# CON1.net
KiCad netlist of a schematic drawn in Altium Designer
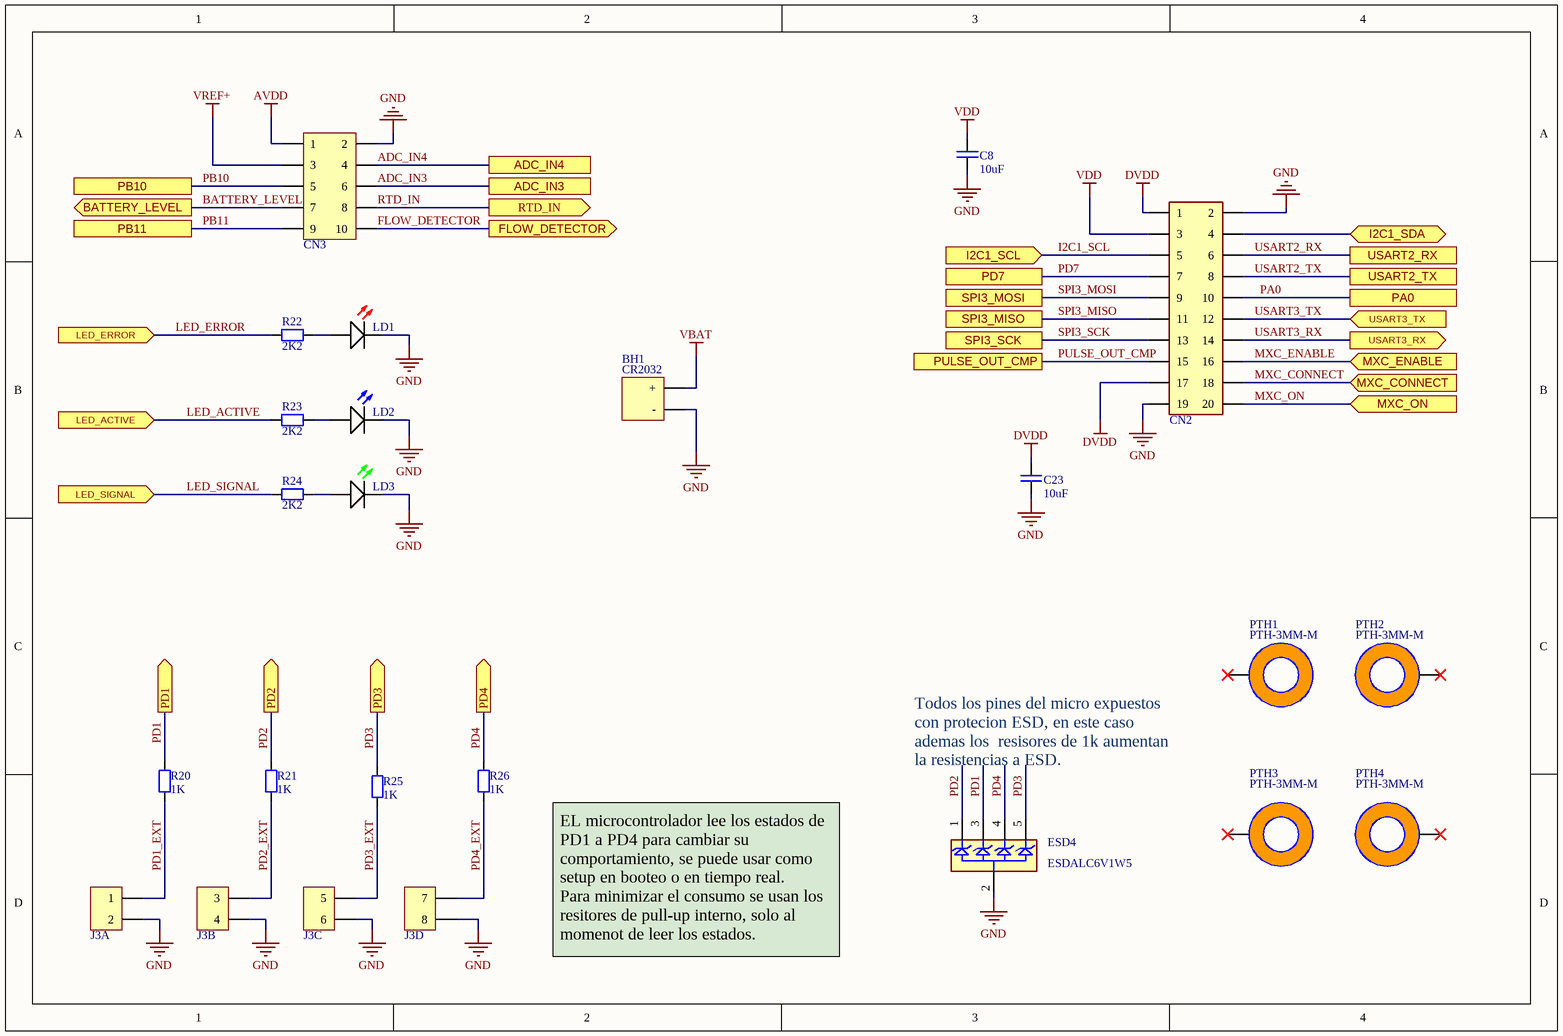
[diagram p0: CON1.SchDoc]

(export (version "E")
  (design (tool "Eeschema 10.0.6"))
  (components
    (comp (ref "BH1")
      (value "CR2032")
      (footprint "BS-08-B2AA016")
      (description "Battery base -25℃~+85℃ CR2032 SMD Battery Connectors ROHS")
      (fields
        (field (name "MANUFACTURER") "Myoung")
        (field (name "MANUFACTURER PART NUMBER") "BS-08-B2AA016")
      )
      (libsource (lib "Battery_Holders") (part "BS-08-B2AA016"))
    )
    (comp (ref "C8")
      (value "10uF")
      (footprint "CAP_SM0805_YAGEOCC2_N")
      (description "CAP 10uF SM0805 X5R 25V YAGEO")
      (fields
        (field (name "MANUFACTURER") "Yageo")
        (field (name "MANUFACTURER PART NUMBER") "CC0805KKX5R8BB106")
      )
      (libsource (lib "Yageo") (part "CC0805KKX5R8BB106"))
    )
    (comp (ref "C23")
      (value "10uF")
      (footprint "CAP_SM0805_YAGEOCC2_N")
      (description "CAP 10uF SM0805 X5R 25V YAGEO")
      (fields
        (field (name "MANUFACTURER") "Yageo")
        (field (name "MANUFACTURER PART NUMBER") "CC0805KKX5R8BB106")
      )
      (libsource (lib "Yageo") (part "CC0805KKX5R8BB106"))
    )
    (comp (ref "CN2")
      (value "DW254R-22-20-85")
      (footprint "DW254R-22-10-85")
      (description "2 x 10 - true hole 2.54mm - altura 8.5mm")
      (fields (field (name "MANUFACTURER") "Dealon"))
      (libsource (lib "header_female") (part "DW254R-22-20-85"))
    )
    (comp (ref "CN3")
      (value "DW254S-22-10-85")
      (footprint "2X5 100 MILS SMD")
      (description "2 x 5 - SMD 2.54mm - altura 8.5mm")
      (fields (field (name "MANUFACTURER") "Dealon"))
      (libsource (lib "header_female") (part "DW254S-22-10-85"))
    )
    (comp (ref "ESD4")
      (value "ESDALC6V1W5")
      (footprint "ESDALC6V1W5")
      (fields (field (name "MANUFACTURER") "ST"))
      (libsource (lib "diode") (part "ESDALC6V1W5"))
    )
    (comp (ref "J3")
      (value "PH2.54-07-04PWS-JUMPER")
      (footprint "HEADER PIN 2X4 A 90 GRADOS")
      (description "2 x 4 - true hole  2.54mm 90°")
      (fields
        (field (name "MANUFACTURER") "XUNPU")
        (field (name "MANUFACTURER PART NUMBER") "PH2.54-07-04PWS")
      )
      (libsource (lib "header_pin") (part "PH2.54-07-04PWS-JUMPER"))
    )
    (comp (ref "LD1")
      (value "ERROR")
      (footprint "LED 0805")
      (fields
        (field (name "MANUFACTURER") "Everlight Elec")
        (field (name "MANUFACTURER PART NUMBER") "17-21SURC/S530-A2/TR8")
      )
      (libsource (lib "LED") (part "17-21SURC/S530-A2/TR8"))
    )
    (comp (ref "LD2")
      (value "RUN")
      (footprint "LED 0805")
      (fields
        (field (name "MANUFACTURER") "Everlight Elec")
        (field (name "MANUFACTURER PART NUMBER") "17-21/BHC-XL2M2TY")
      )
      (libsource (lib "LED") (part "17-21/BHC-XL2M2TY/3T"))
    )
    (comp (ref "LD3")
      (value "SGINAL")
      (footprint "LED 0805")
      (fields
        (field (name "MANUFACTURER") "Everlight Elec")
        (field (name "MANUFACTURER PART NUMBER") "17-21SYGC/S530-E2/TR8")
      )
      (libsource (lib "LED") (part "17-21SYGC/S530-E2/TR8"))
    )
    (comp (ref "PTH1")
      (value "PTH-3MM-M")
      (footprint "PTH_M3_M")
      (description "Agujero de montaje metalizado roscas M3. Drill de tamaño medio.")
      (libsource (lib "montaje") (part "PTH-3MM-M"))
    )
    (comp (ref "PTH2")
      (value "PTH-3MM-M")
      (footprint "PTH_M3_M")
      (description "Agujero de montaje metalizado roscas M3. Drill de tamaño medio.")
      (libsource (lib "montaje") (part "PTH-3MM-M"))
    )
    (comp (ref "PTH3")
      (value "PTH-3MM-M")
      (footprint "PTH_M3_M")
      (description "Agujero de montaje metalizado roscas M3. Drill de tamaño medio.")
      (libsource (lib "montaje") (part "PTH-3MM-M"))
    )
    (comp (ref "PTH4")
      (value "PTH-3MM-M")
      (footprint "PTH_M3_M")
      (description "Agujero de montaje metalizado roscas M3. Drill de tamaño medio.")
      (libsource (lib "montaje") (part "PTH-3MM-M"))
    )
    (comp (ref "R20")
      (value "1K")
      (footprint "RES_SM0805_YAGEORC_N")
      (description "RES 1K SM0805 YAGEO RC_L")
      (fields
        (field (name "MANUFACTURER") "Yageo")
        (field (name "MANUFACTURER PART NUMBER") "RC0805FR-071KL")
      )
      (libsource (lib "Yageo") (part "RC0805FR-071KL"))
    )
    (comp (ref "R21")
      (value "1K")
      (footprint "RES_SM0805_YAGEORC_N")
      (description "RES 1K SM0805 YAGEO RC_L")
      (fields
        (field (name "MANUFACTURER") "Yageo")
        (field (name "MANUFACTURER PART NUMBER") "RC0805FR-071KL")
      )
      (libsource (lib "Yageo") (part "RC0805FR-071KL"))
    )
    (comp (ref "R22")
      (value "2K2")
      (footprint "RES_SM0805_YAGEORC_N")
      (description "RES 2K2 SM0805 YAGEO RC_L")
      (fields
        (field (name "MANUFACTURER") "Yageo")
        (field (name "MANUFACTURER PART NUMBER") "RC0805FR-072K2L")
      )
      (libsource (lib "Yageo") (part "RC0805FR-072K2L"))
    )
    (comp (ref "R23")
      (value "2K2")
      (footprint "RES_SM0805_YAGEORC_N")
      (description "RES 2K2 SM0805 YAGEO RC_L")
      (fields
        (field (name "MANUFACTURER") "Yageo")
        (field (name "MANUFACTURER PART NUMBER") "RC0805FR-072K2L")
      )
      (libsource (lib "Yageo") (part "RC0805FR-072K2L"))
    )
    (comp (ref "R24")
      (value "2K2")
      (footprint "RES_SM0805_YAGEORC_N")
      (description "RES 2K2 SM0805 YAGEO RC_L")
      (fields
        (field (name "MANUFACTURER") "Yageo")
        (field (name "MANUFACTURER PART NUMBER") "RC0805FR-072K2L")
      )
      (libsource (lib "Yageo") (part "RC0805FR-072K2L"))
    )
    (comp (ref "R25")
      (value "1K")
      (footprint "RES_SM0805_YAGEORC_N")
      (description "RES 1K SM0805 YAGEO RC_L")
      (fields
        (field (name "MANUFACTURER") "Yageo")
        (field (name "MANUFACTURER PART NUMBER") "RC0805FR-071KL")
      )
      (libsource (lib "Yageo") (part "RC0805FR-071KL"))
    )
    (comp (ref "R26")
      (value "1K")
      (footprint "RES_SM0805_YAGEORC_N")
      (description "RES 1K SM0805 YAGEO RC_L")
      (fields
        (field (name "MANUFACTURER") "Yageo")
        (field (name "MANUFACTURER PART NUMBER") "RC0805FR-071KL")
      )
      (libsource (lib "Yageo") (part "RC0805FR-071KL"))
    )
  )
  (nets
    (net (code "1") (name "/ADC_IN3") (class "Default")
      (node (ref "CN3") (pin "6") (pinfunction "6_6") (pintype "passive"))
    )
    (net (code "2") (name "/ADC_IN4") (class "Default")
      (node (ref "CN3") (pin "4") (pinfunction "4_4") (pintype "passive"))
    )
    (net (code "3") (name "/BATTERY_LEVEL") (class "Default")
      (node (ref "CN3") (pin "7") (pinfunction "7_7") (pintype "passive"))
    )
    (net (code "4") (name "/FLOW_DETECTOR") (class "Default")
      (node (ref "CN3") (pin "10") (pinfunction "10_10") (pintype "passive"))
    )
    (net (code "5") (name "/I2C1_SCL") (class "Default")
      (node (ref "CN2") (pin "5") (pinfunction "5_5") (pintype "passive"))
    )
    (net (code "6") (name "/I2C1_SDA") (class "Default")
      (node (ref "CN2") (pin "4") (pinfunction "4_4") (pintype "passive"))
    )
    (net (code "7") (name "/LED_ACTIVE") (class "Default") (node (ref "R23") (pin "1") (pintype "passive")))
    (net (code "8") (name "/LED_ERROR") (class "Default") (node (ref "R22") (pin "1") (pintype "passive")))
    (net (code "9") (name "/LED_SIGNAL") (class "Default") (node (ref "R24") (pin "1") (pintype "passive")))
    (net (code "10") (name "/MXC_CONNECT") (class "Default")
      (node (ref "CN2") (pin "18") (pinfunction "18_18") (pintype "passive"))
    )
    (net (code "11") (name "/MXC_ENABLE") (class "Default")
      (node (ref "CN2") (pin "16") (pinfunction "16_16") (pintype "passive"))
    )
    (net (code "12") (name "/MXC_ON") (class "Default")
      (node (ref "CN2") (pin "20") (pinfunction "20_20") (pintype "passive"))
    )
    (net (code "13") (name "/PA0") (class "Default")
      (node (ref "CN2") (pin "10") (pinfunction "10_10") (pintype "passive"))
    )
    (net (code "14") (name "/PB10") (class "Default")
      (node (ref "CN3") (pin "5") (pinfunction "5_5") (pintype "passive"))
    )
    (net (code "15") (name "/PB11") (class "Default")
      (node (ref "CN3") (pin "9") (pinfunction "9_9") (pintype "passive"))
    )
    (net (code "16") (name "/PD1") (class "Default")
      (node (ref "ESD4") (pin "3") (pinfunction "I/02_3") (pintype "passive"))
      (node (ref "R20") (pin "2") (pintype "passive"))
    )
    (net (code "17") (name "/PD1_EXT") (class "Default")
      (node (ref "J3") (pin "1") (pinfunction "1_1") (pintype "passive"))
      (node (ref "R20") (pin "1") (pintype "passive"))
    )
    (net (code "18") (name "/PD2") (class "Default")
      (node (ref "ESD4") (pin "1") (pinfunction "I/01_1") (pintype "passive"))
      (node (ref "R21") (pin "2") (pintype "passive"))
    )
    (net (code "19") (name "/PD2_EXT") (class "Default")
      (node (ref "J3") (pin "3") (pinfunction "3_3") (pintype "passive"))
      (node (ref "R21") (pin "1") (pintype "passive"))
    )
    (net (code "20") (name "/PD3") (class "Default")
      (node (ref "ESD4") (pin "5") (pinfunction "I/04_5") (pintype "passive"))
      (node (ref "R25") (pin "2") (pintype "passive"))
    )
    (net (code "21") (name "/PD3_EXT") (class "Default")
      (node (ref "J3") (pin "5") (pinfunction "5_5") (pintype "passive"))
      (node (ref "R25") (pin "1") (pintype "passive"))
    )
    (net (code "22") (name "/PD4") (class "Default")
      (node (ref "ESD4") (pin "4") (pinfunction "I/03_4") (pintype "passive"))
      (node (ref "R26") (pin "2") (pintype "passive"))
    )
    (net (code "23") (name "/PD4_EXT") (class "Default")
      (node (ref "J3") (pin "7") (pinfunction "7_7") (pintype "passive"))
      (node (ref "R26") (pin "1") (pintype "passive"))
    )
    (net (code "24") (name "/PD7") (class "Default")
      (node (ref "CN2") (pin "7") (pinfunction "7_7") (pintype "passive"))
    )
    (net (code "25") (name "/PULSE_OUT_CMP") (class "Default")
      (node (ref "CN2") (pin "15") (pinfunction "15_15") (pintype "passive"))
    )
    (net (code "26") (name "/RTD_IN") (class "Default")
      (node (ref "CN3") (pin "8") (pinfunction "8_8") (pintype "passive"))
    )
    (net (code "27") (name "/SPI3_MISO") (class "Default")
      (node (ref "CN2") (pin "11") (pinfunction "11_11") (pintype "passive"))
    )
    (net (code "28") (name "/SPI3_MOSI") (class "Default")
      (node (ref "CN2") (pin "9") (pinfunction "9_9") (pintype "passive"))
    )
    (net (code "29") (name "/SPI3_SCK") (class "Default")
      (node (ref "CN2") (pin "13") (pinfunction "13_13") (pintype "passive"))
    )
    (net (code "30") (name "/USART2_RX") (class "Default")
      (node (ref "CN2") (pin "6") (pinfunction "6_6") (pintype "passive"))
    )
    (net (code "31") (name "/USART2_TX") (class "Default")
      (node (ref "CN2") (pin "8") (pinfunction "8_8") (pintype "passive"))
    )
    (net (code "32") (name "/USART3_RX") (class "Default")
      (node (ref "CN2") (pin "14") (pinfunction "14_14") (pintype "passive"))
    )
    (net (code "33") (name "/USART3_TX") (class "Default")
      (node (ref "CN2") (pin "12") (pinfunction "12_12") (pintype "passive"))
    )
    (net (code "34") (name "AVDD") (class "Default")
      (node (ref "CN3") (pin "1") (pinfunction "1_1") (pintype "passive"))
    )
    (net (code "35") (name "DVDD") (class "Default")
      (node (ref "C23") (pin "2") (pintype "passive"))
      (node (ref "CN2") (pin "1") (pinfunction "1_1") (pintype "passive"))
      (node (ref "CN2") (pin "17") (pinfunction "17_17") (pintype "passive"))
    )
    (net (code "36") (name "GND") (class "Default")
      (node (ref "BH1") (pin "NEG") (pinfunction "-_NEG") (pintype "passive"))
      (node (ref "C23") (pin "1") (pintype "passive"))
      (node (ref "C8") (pin "1") (pintype "passive"))
      (node (ref "CN2") (pin "19") (pinfunction "19_19") (pintype "passive"))
      (node (ref "CN2") (pin "2") (pinfunction "2_2") (pintype "passive"))
      (node (ref "CN3") (pin "2") (pinfunction "2_2") (pintype "passive"))
      (node (ref "ESD4") (pin "2") (pinfunction "GND_2") (pintype "passive"))
      (node (ref "J3") (pin "2") (pinfunction "2_2") (pintype "passive"))
      (node (ref "J3") (pin "4") (pinfunction "4_4") (pintype "passive"))
      (node (ref "J3") (pin "6") (pinfunction "6_6") (pintype "passive"))
      (node (ref "J3") (pin "8") (pinfunction "8_8") (pintype "passive"))
      (node (ref "LD1") (pin "K") (pinfunction "K_K") (pintype "passive"))
      (node (ref "LD2") (pin "K") (pinfunction "K_K") (pintype "passive"))
      (node (ref "LD3") (pin "K") (pinfunction "K_K") (pintype "passive"))
    )
    (net (code "37") (name "Net-(LD1-PadA)") (class "Default")
      (node (ref "LD1") (pin "A") (pinfunction "A_A") (pintype "passive"))
      (node (ref "R22") (pin "2") (pintype "passive"))
    )
    (net (code "38") (name "Net-(LD2-PadA)") (class "Default")
      (node (ref "LD2") (pin "A") (pinfunction "A_A") (pintype "passive"))
      (node (ref "R23") (pin "2") (pintype "passive"))
    )
    (net (code "39") (name "Net-(LD3-PadA)") (class "Default")
      (node (ref "LD3") (pin "A") (pinfunction "A_A") (pintype "passive"))
      (node (ref "R24") (pin "2") (pintype "passive"))
    )
    (net (code "40") (name "VBAT") (class "Default")
      (node (ref "BH1") (pin "POS") (pinfunction "+_POS") (pintype "passive"))
    )
    (net (code "41") (name "VDD") (class "Default")
      (node (ref "C8") (pin "2") (pintype "passive"))
      (node (ref "CN2") (pin "3") (pinfunction "3_3") (pintype "passive"))
    )
    (net (code "42") (name "VREF+") (class "Default")
      (node (ref "CN3") (pin "3") (pinfunction "3_3") (pintype "passive"))
    )
    (net (code "43") (name "unconnected-(PTH1-Pad1)") (class "Default")
      (node (ref "PTH1") (pin "1") (pinfunction "1_1") (pintype "passive+no_connect"))
    )
    (net (code "44") (name "unconnected-(PTH2-Pad1)") (class "Default")
      (node (ref "PTH2") (pin "1") (pinfunction "1_1") (pintype "passive+no_connect"))
    )
    (net (code "45") (name "unconnected-(PTH3-Pad1)") (class "Default")
      (node (ref "PTH3") (pin "1") (pinfunction "1_1") (pintype "passive+no_connect"))
    )
    (net (code "46") (name "unconnected-(PTH4-Pad1)") (class "Default")
      (node (ref "PTH4") (pin "1") (pinfunction "1_1") (pintype "passive+no_connect"))
    )
  )
)
